# B6_32D_20230728.net
KiCad netlist of a schematic drawn in Altium Designer
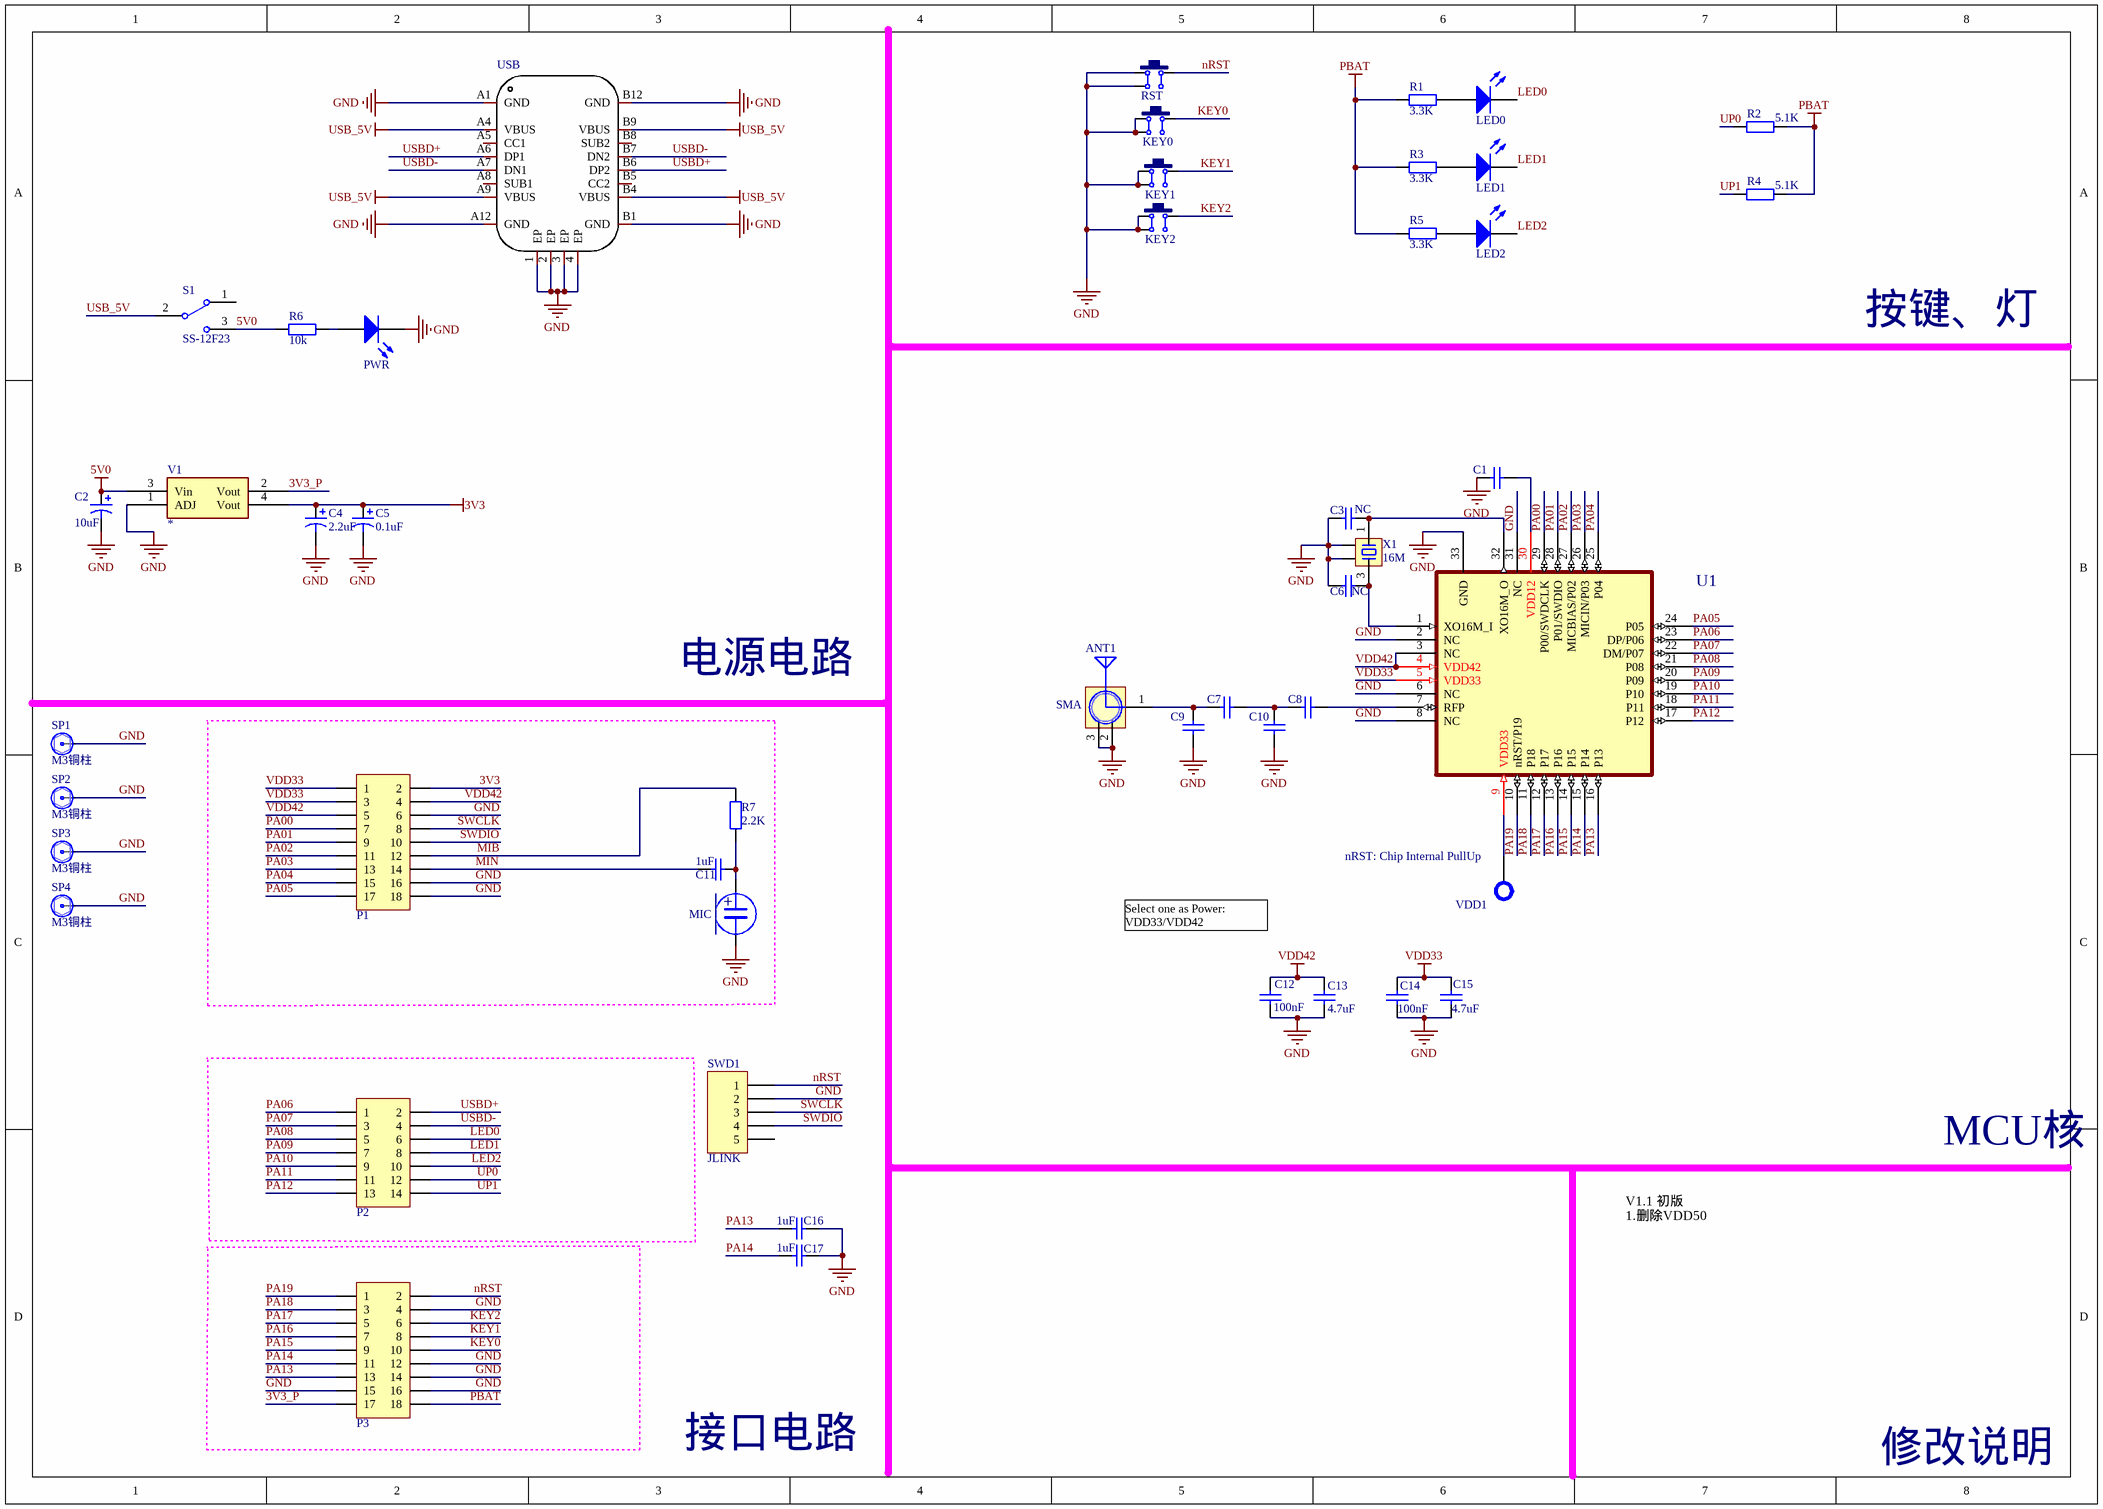
[diagram p0: B6_32D_20230728.SchDoc]

(export (version "E")
  (design (tool "Eeschema 10.0.6"))
  (components
    (comp (ref "ANT1")
      (value "SMA")
      (footprint "SMA-KE-LI")
      (description "SMA-2.4G射频天线接口")
      (libsource (lib "1.8 - WiFi天线-SMA射频座") (part "SMA"))
    )
    (comp (ref "C1")
      (value "NC")
      (footprint "C0603")
      (description "Capacitor (Semiconductor SIM Model)")
      (libsource (lib "HYBXX_Dragon") (part "Cap"))
    )
    (comp (ref "C2")
      (value "10uF")
      (footprint "HYBXX_Dragon:C0603")
      (description "Polarized Capacitor (Surface Mount)")
      (fields (field (name "PUBLISHER") "Altium Limited"))
      (libsource (lib "HYBXX_Dragon") (part "Cap Pol3"))
    )
    (comp (ref "C3")
      (value "NC")
      (footprint "C0603")
      (description "Capacitor (Semiconductor SIM Model)")
      (libsource (lib "HYBXX_Dragon") (part "Cap"))
    )
    (comp (ref "C4")
      (value "2.2uF")
      (footprint "HYBXX_Dragon:C0603")
      (description "Polarized Capacitor (Surface Mount)")
      (fields (field (name "PUBLISHER") "Altium Limited"))
      (libsource (lib "HYBXX_Dragon") (part "Cap Pol3"))
    )
    (comp (ref "C5")
      (value "0.1uF")
      (footprint "HYBXX_Dragon:C0603")
      (description "Polarized Capacitor (Surface Mount)")
      (fields (field (name "PUBLISHER") "Altium Limited"))
      (libsource (lib "HYBXX_Dragon") (part "Cap Pol3"))
    )
    (comp (ref "C6")
      (value "NC")
      (footprint "C0603")
      (description "Capacitor (Semiconductor SIM Model)")
      (libsource (lib "HYBXX_Dragon") (part "Cap"))
    )
    (comp (ref "C7")
      (value "0")
      (footprint "C0402")
      (description "Capacitor (Semiconductor SIM Model)")
      (libsource (lib "HYBXX_Dragon") (part "Cap"))
    )
    (comp (ref "C8")
      (value "0")
      (footprint "C0402")
      (description "Capacitor (Semiconductor SIM Model)")
      (libsource (lib "HYBXX_Dragon") (part "Cap"))
    )
    (comp (ref "C9")
      (value "0")
      (footprint "C0402")
      (description "Capacitor (Semiconductor SIM Model)")
      (libsource (lib "HYBXX_Dragon") (part "Cap"))
    )
    (comp (ref "C10")
      (value "0")
      (footprint "C0402")
      (description "Capacitor (Semiconductor SIM Model)")
      (libsource (lib "HYBXX_Dragon") (part "Cap"))
    )
    (comp (ref "C11")
      (value "1uF")
      (footprint "C0603")
      (description "Capacitor (Semiconductor SIM Model)")
      (libsource (lib "HYBXX_Dragon") (part "Cap"))
    )
    (comp (ref "C12")
      (value "100nF")
      (footprint "C0603")
      (description "Capacitor (Semiconductor SIM Model)")
      (libsource (lib "HYBXX_Dragon") (part "Cap"))
    )
    (comp (ref "C13")
      (value "4.7uF")
      (footprint "C0603")
      (description "Capacitor (Semiconductor SIM Model)")
      (libsource (lib "HYBXX_Dragon") (part "Cap"))
    )
    (comp (ref "C14")
      (value "100nF")
      (footprint "C0603")
      (description "Capacitor (Semiconductor SIM Model)")
      (fields (field (name "PUBLISHER") "Altium Limited"))
      (libsource (lib "Miscellaneous Devices") (part "Cap Semi"))
    )
    (comp (ref "C15")
      (value "4.7uF")
      (footprint "C0603")
      (description "Capacitor (Semiconductor SIM Model)")
      (libsource (lib "HYBXX_Dragon") (part "Cap"))
    )
    (comp (ref "C16")
      (value "1uF")
      (footprint "C0603")
      (description "Capacitor (Semiconductor SIM Model)")
      (libsource (lib "HYBXX_Dragon") (part "Cap"))
    )
    (comp (ref "C17")
      (value "1uF")
      (footprint "C0603")
      (description "Capacitor (Semiconductor SIM Model)")
      (libsource (lib "HYBXX_Dragon") (part "Cap"))
    )
    (comp (ref "KEY0")
      (value "6x6x5")
      (footprint "SW-SMD")
      (description "贴片6x6轻触开关")
      (fields (field (name "版权归属") "封装库来自淘宝 ID：黄晶宝石"))
      (libsource (lib "0.7 - 常用按键-开关") (part "TSW SMD-6x6"))
    )
    (comp (ref "KEY1")
      (value "6x6x5")
      (footprint "SW-SMD")
      (description "贴片6x6轻触开关")
      (fields (field (name "版权归属") "封装库来自淘宝 ID：黄晶宝石"))
      (libsource (lib "0.7 - 常用按键-开关") (part "TSW SMD-6x6"))
    )
    (comp (ref "KEY2")
      (value "6x6x5")
      (footprint "SW-SMD")
      (description "贴片6x6轻触开关")
      (fields (field (name "版权归属") "封装库来自淘宝 ID：黄晶宝石"))
      (libsource (lib "0.7 - 常用按键-开关") (part "TSW SMD-6x6"))
    )
    (comp (ref "LED0")
      (value "*")
      (footprint "LED_0603")
      (description "发光二极管")
      (libsource (lib "HYBXX_Dragon") (part "LED"))
    )
    (comp (ref "LED1")
      (value "*")
      (footprint "LED_0603")
      (description "发光二极管")
      (libsource (lib "HYBXX_Dragon") (part "LED"))
    )
    (comp (ref "LED2")
      (value "*")
      (footprint "LED_0603")
      (description "发光二极管")
      (libsource (lib "HYBXX_Dragon") (part "LED"))
    )
    (comp (ref "MIC")
      (value "MIC-6*5mm")
      (footprint "MIC-6*5.5mm")
      (description "电容麦克风")
      (fields (field (name "版权归属") "封装库来自淘宝 ID：黄晶宝石"))
      (libsource (lib "1.2 - 传感元件") (part "MIC1"))
    )
    (comp (ref "P1")
      (value "Header 2X11")
      (footprint "HDR2.54-LI-2x9P")
      (description "9*2P接插件")
      (fields (field (name "版权归属") "淘宝ID:黄晶宝石"))
      (libsource (lib "5.3 - 接插件-脚距2.54 (100mil) ") (part "Header 9X2"))
    )
    (comp (ref "P2")
      (value "Header 2X7")
      (footprint "HDR2.54-LI-2x7P")
      (description "7*2P接插件")
      (fields (field (name "版权归属") "封装库来自淘宝 ID：黄晶宝石"))
      (libsource (lib "5.3 - 接插件-脚距2.54 (100mil) ") (part "Header 7X2"))
    )
    (comp (ref "P3")
      (value "Header 2X11")
      (footprint "HDR2.54-LI-2x9P")
      (description "9*2P接插件")
      (fields (field (name "版权归属") "淘宝ID:黄晶宝石"))
      (libsource (lib "5.3 - 接插件-脚距2.54 (100mil) ") (part "Header 9X2"))
    )
    (comp (ref "PWR")
      (value "*")
      (footprint "LED_0603")
      (description "发光二极管")
      (libsource (lib "HYBXX_Dragon") (part "LED"))
    )
    (comp (ref "R1")
      (value "3.3K")
      (footprint "R 0603_L")
      (description "贴片电阻")
      (libsource (lib "HYBXX_Dragon") (part "Res"))
    )
    (comp (ref "R2")
      (value "5.1K")
      (footprint "R 0603_L")
      (description "贴片电阻")
      (libsource (lib "") (part "Res_1"))
    )
    (comp (ref "R3")
      (value "3.3K")
      (footprint "R 0603_L")
      (description "贴片电阻")
      (libsource (lib "HYBXX_Dragon") (part "Res"))
    )
    (comp (ref "R4")
      (value "5.1K")
      (footprint "R 0603_L")
      (description "贴片电阻")
      (libsource (lib "") (part "Res_1"))
    )
    (comp (ref "R5")
      (value "3.3K")
      (footprint "R 0603_L")
      (description "贴片电阻")
      (libsource (lib "HYBXX_Dragon") (part "Res"))
    )
    (comp (ref "R6")
      (value "10k")
      (footprint "RESC_0603")
      (description "贴片电阻")
      (libsource (lib "HYBXX_Dragon") (part "Res"))
    )
    (comp (ref "R7")
      (value "2.2K")
      (footprint "R 0603_L")
      (description "贴片电阻")
      (libsource (lib "") (part "Res_1"))
    )
    (comp (ref "RST")
      (value "6x6x5")
      (footprint "SW-SMD")
      (description "贴片6x6轻触开关")
      (fields (field (name "版权归属") "封装库来自淘宝 ID：黄晶宝石"))
      (libsource (lib "0.7 - 常用按键-开关") (part "TSW SMD-6x6"))
    )
    (comp (ref "S1")
      (value "SS-12F23")
      (footprint "SK12D07VG3")
      (description "1路波动开关")
      (fields (field (name "版权归属") "封装库来自淘宝 ID：黄晶宝石"))
      (libsource (lib "0.7 - 常用按键-开关") (part "SSW-1P"))
    )
    (comp (ref "SP1")
      (value "M3铜柱")
      (footprint "M3x21+6_L")
      (description "铜柱")
      (libsource (lib "4.1 - 未分类器件") (part "铜柱加头小焊盘"))
    )
    (comp (ref "SP2")
      (value "M3铜柱")
      (footprint "M3x21+6_L")
      (description "铜柱")
      (fields (field (name "版权归属") "封装库来自淘宝 ID：黄晶宝石"))
      (libsource (lib "4.1 - 未分类器件") (part "铜柱加头小焊盘"))
    )
    (comp (ref "SP3")
      (value "M3铜柱")
      (footprint "M3x21+6_L")
      (description "铜柱")
      (fields (field (name "版权归属") "封装库来自淘宝 ID：黄晶宝石"))
      (libsource (lib "4.1 - 未分类器件") (part "铜柱加头小焊盘"))
    )
    (comp (ref "SP4")
      (value "M3铜柱")
      (footprint "M3x21+6_L")
      (description "铜柱")
      (fields (field (name "版权归属") "封装库来自淘宝 ID：黄晶宝石"))
      (libsource (lib "4.1 - 未分类器件") (part "铜柱加头小焊盘"))
    )
    (comp (ref "SWD1")
      (value "JLINK")
      (footprint "HDR2.54-LI-5P")
      (description "Header, 5-Pin")
      (fields (field (name "PUBLISHER") "Altium Limited"))
      (libsource (lib "5.3 - 接插件-脚距2.54 (100mil) ") (part "Header 5"))
    )
    (comp (ref "U1")
      (value "C1_QFN32")
      (footprint "QFN32L_0404x0.75-0.40")
      (description "HY Dragon C 蓝牙芯片, QFN32_4x4")
      (libsource (lib "HYBXX_Dragon") (part "C1_QFN32"))
    )
    (comp (ref "USB")
      (value "KH-TYPE-C-16P")
      (footprint "USB-C-SMD_KH-TYPE-C-16P")
      (description "连接器类型:Type-C;标准:-;公母:母座;触点数量:16;端口数量:1;安装方式:卧贴;额定电流 - 电源:3A;工作温度范围:-40~+85;")
      (fields (field (name "MANUFACTURER") "kinghelm(金航标)"))
      (libsource (lib "altium-import") (part "root_0_KH-TYPE-C-16P_"))
    )
    (comp (ref "V1")
      (value "*")
      (footprint "SOT223_L")
      (description "LDO 可调节稳压芯片")
      (libsource (lib "HYBXX_Dragon") (part "AMS1117"))
    )
    (comp (ref "VDD1")
      (value "HOLE")
      (footprint "HYBXX_Dragon:TEST_PAD")
      (description "定位孔")
      (libsource (lib "HYBXX_Dragon") (part "HOLE"))
    )
    (comp (ref "X1")
      (value "16M")
      (footprint "OSC3225-mini")
      (description "4脚无源晶振")
      (fields (field (name "版权归属") "封装库来自淘宝卖家 ID：黄晶宝石"))
      (libsource (lib "2.0 - 保险丝-晶振-光耦") (part "XTAL-4P"))
    )
  )
  (nets
    (net (code "1") (name "/3V3_P") (class "Default")
      (node (ref "P3") (pin "17") (pinfunction "17_17") (pintype "passive"))
      (node (ref "V1") (pin "2") (pinfunction "Vout_2") (pintype "passive"))
    )
    (net (code "2") (name "/KEY0") (class "Default")
      (node (ref "KEY0") (pin "2") (pinfunction "2_2") (pintype "passive"))
      (node (ref "P3") (pin "10") (pinfunction "10_10") (pintype "passive"))
    )
    (net (code "3") (name "/KEY1") (class "Default")
      (node (ref "KEY1") (pin "2") (pinfunction "2_2") (pintype "passive"))
      (node (ref "P3") (pin "8") (pinfunction "8_8") (pintype "passive"))
    )
    (net (code "4") (name "/KEY2") (class "Default")
      (node (ref "KEY2") (pin "2") (pinfunction "2_2") (pintype "passive"))
      (node (ref "P3") (pin "6") (pinfunction "6_6") (pintype "passive"))
    )
    (net (code "5") (name "/LED0") (class "Default")
      (node (ref "LED0") (pin "2") (pinfunction "K_2") (pintype "passive"))
      (node (ref "P2") (pin "6") (pinfunction "6_6") (pintype "passive"))
    )
    (net (code "6") (name "/LED1") (class "Default")
      (node (ref "LED1") (pin "2") (pinfunction "K_2") (pintype "passive"))
      (node (ref "P2") (pin "8") (pinfunction "8_8") (pintype "passive"))
    )
    (net (code "7") (name "/LED2") (class "Default")
      (node (ref "LED2") (pin "2") (pinfunction "K_2") (pintype "passive"))
      (node (ref "P2") (pin "10") (pinfunction "10_10") (pintype "passive"))
    )
    (net (code "8") (name "/MIB") (class "Default")
      (node (ref "P1") (pin "12") (pinfunction "12_12") (pintype "passive"))
      (node (ref "R7") (pin "1") (pinfunction "1_1") (pintype "passive"))
    )
    (net (code "9") (name "/MIN") (class "Default")
      (node (ref "C11") (pin "2") (pinfunction "2_2") (pintype "passive"))
      (node (ref "P1") (pin "14") (pinfunction "14_14") (pintype "passive"))
    )
    (net (code "10") (name "/PA00") (class "Default")
      (node (ref "P1") (pin "7") (pinfunction "7_7") (pintype "passive"))
      (node (ref "U1") (pin "29") (pinfunction "P00/SWDCLK_29") (pintype "bidirectional"))
    )
    (net (code "11") (name "/PA01") (class "Default")
      (node (ref "P1") (pin "9") (pinfunction "9_9") (pintype "passive"))
      (node (ref "U1") (pin "28") (pinfunction "P01/SWDIO_28") (pintype "bidirectional"))
    )
    (net (code "12") (name "/PA02") (class "Default")
      (node (ref "P1") (pin "11") (pinfunction "11_11") (pintype "passive"))
      (node (ref "U1") (pin "27") (pinfunction "MICBIAS/P02_27") (pintype "bidirectional"))
    )
    (net (code "13") (name "/PA03") (class "Default")
      (node (ref "P1") (pin "13") (pinfunction "13_13") (pintype "passive"))
      (node (ref "U1") (pin "26") (pinfunction "MICIN/P03_26") (pintype "bidirectional"))
    )
    (net (code "14") (name "/PA04") (class "Default")
      (node (ref "P1") (pin "15") (pinfunction "15_15") (pintype "passive"))
      (node (ref "U1") (pin "25") (pinfunction "P04_25") (pintype "bidirectional"))
    )
    (net (code "15") (name "/PA05") (class "Default")
      (node (ref "P1") (pin "17") (pinfunction "17_17") (pintype "passive"))
      (node (ref "U1") (pin "24") (pinfunction "P05_24") (pintype "bidirectional"))
    )
    (net (code "16") (name "/PA06") (class "Default")
      (node (ref "P2") (pin "1") (pinfunction "1_1") (pintype "passive"))
      (node (ref "U1") (pin "23") (pinfunction "DP/P06_23") (pintype "bidirectional"))
    )
    (net (code "17") (name "/PA07") (class "Default")
      (node (ref "P2") (pin "3") (pinfunction "3_3") (pintype "passive"))
      (node (ref "U1") (pin "22") (pinfunction "DM/P07_22") (pintype "bidirectional"))
    )
    (net (code "18") (name "/PA08") (class "Default")
      (node (ref "P2") (pin "5") (pinfunction "5_5") (pintype "passive"))
      (node (ref "U1") (pin "21") (pinfunction "P08_21") (pintype "bidirectional"))
    )
    (net (code "19") (name "/PA09") (class "Default")
      (node (ref "P2") (pin "7") (pinfunction "7_7") (pintype "passive"))
      (node (ref "U1") (pin "20") (pinfunction "P09_20") (pintype "bidirectional"))
    )
    (net (code "20") (name "/PA10") (class "Default")
      (node (ref "P2") (pin "9") (pinfunction "9_9") (pintype "passive"))
      (node (ref "U1") (pin "19") (pinfunction "P10_19") (pintype "bidirectional"))
    )
    (net (code "21") (name "/PA11") (class "Default")
      (node (ref "P2") (pin "11") (pinfunction "11_11") (pintype "passive"))
      (node (ref "U1") (pin "18") (pinfunction "P11_18") (pintype "bidirectional"))
    )
    (net (code "22") (name "/PA12") (class "Default")
      (node (ref "P2") (pin "13") (pinfunction "13_13") (pintype "passive"))
      (node (ref "U1") (pin "17") (pinfunction "P12_17") (pintype "bidirectional"))
    )
    (net (code "23") (name "/PA13") (class "Default")
      (node (ref "C16") (pin "2") (pinfunction "2_2") (pintype "passive"))
      (node (ref "P3") (pin "13") (pinfunction "13_13") (pintype "passive"))
      (node (ref "U1") (pin "16") (pinfunction "P13_16") (pintype "bidirectional"))
    )
    (net (code "24") (name "/PA14") (class "Default")
      (node (ref "C17") (pin "2") (pinfunction "2_2") (pintype "passive"))
      (node (ref "P3") (pin "11") (pinfunction "11_11") (pintype "passive"))
      (node (ref "U1") (pin "15") (pinfunction "P14_15") (pintype "bidirectional"))
    )
    (net (code "25") (name "/PA15") (class "Default")
      (node (ref "P3") (pin "9") (pinfunction "9_9") (pintype "passive"))
      (node (ref "U1") (pin "14") (pinfunction "P15_14") (pintype "bidirectional"))
    )
    (net (code "26") (name "/PA16") (class "Default")
      (node (ref "P3") (pin "7") (pinfunction "7_7") (pintype "passive"))
      (node (ref "U1") (pin "13") (pinfunction "P16_13") (pintype "bidirectional"))
    )
    (net (code "27") (name "/PA17") (class "Default")
      (node (ref "P3") (pin "5") (pinfunction "5_5") (pintype "passive"))
      (node (ref "U1") (pin "12") (pinfunction "P17_12") (pintype "bidirectional"))
    )
    (net (code "28") (name "/PA18") (class "Default")
      (node (ref "P3") (pin "3") (pinfunction "3_3") (pintype "passive"))
      (node (ref "U1") (pin "11") (pinfunction "P18_11") (pintype "bidirectional"))
    )
    (net (code "29") (name "/PA19") (class "Default")
      (node (ref "P3") (pin "1") (pinfunction "1_1") (pintype "passive"))
      (node (ref "U1") (pin "10") (pinfunction "nRST/P19_10") (pintype "bidirectional"))
    )
    (net (code "30") (name "/SWCLK") (class "Default")
      (node (ref "P1") (pin "8") (pinfunction "8_8") (pintype "passive"))
      (node (ref "SWD1") (pin "3") (pinfunction "3_3") (pintype "passive"))
    )
    (net (code "31") (name "/SWDIO") (class "Default")
      (node (ref "P1") (pin "10") (pinfunction "10_10") (pintype "passive"))
      (node (ref "SWD1") (pin "4") (pinfunction "4_4") (pintype "passive"))
    )
    (net (code "32") (name "/UP0") (class "Default")
      (node (ref "P2") (pin "12") (pinfunction "12_12") (pintype "passive"))
      (node (ref "R2") (pin "2") (pinfunction "2_2") (pintype "passive"))
    )
    (net (code "33") (name "/UP1") (class "Default")
      (node (ref "P2") (pin "14") (pinfunction "14_14") (pintype "passive"))
      (node (ref "R4") (pin "2") (pinfunction "2_2") (pintype "passive"))
    )
    (net (code "34") (name "/USBD+") (class "Default")
      (node (ref "P2") (pin "2") (pinfunction "2_2") (pintype "passive"))
      (node (ref "USB") (pin "A6") (pinfunction "DP1_A6") (pintype "passive"))
      (node (ref "USB") (pin "B6") (pinfunction "DP2_B6") (pintype "passive"))
    )
    (net (code "35") (name "/USBD-") (class "Default")
      (node (ref "P2") (pin "4") (pinfunction "4_4") (pintype "passive"))
      (node (ref "USB") (pin "A7") (pinfunction "DN1_A7") (pintype "passive"))
      (node (ref "USB") (pin "B7") (pinfunction "DN2_B7") (pintype "passive"))
    )
    (net (code "36") (name "/nRST") (class "Default")
      (node (ref "P3") (pin "2") (pinfunction "2_2") (pintype "passive"))
      (node (ref "RST") (pin "2") (pinfunction "2_2") (pintype "passive"))
      (node (ref "SWD1") (pin "1") (pinfunction "1_1") (pintype "passive"))
    )
    (net (code "37") (name "3V3") (class "Default")
      (node (ref "C4") (pin "1") (pinfunction "1_1") (pintype "passive"))
      (node (ref "C5") (pin "1") (pinfunction "1_1") (pintype "passive"))
      (node (ref "P1") (pin "2") (pinfunction "2_2") (pintype "passive"))
      (node (ref "V1") (pin "4") (pinfunction "Vout_4") (pintype "passive"))
    )
    (net (code "38") (name "5V0") (class "Default")
      (node (ref "C2") (pin "1") (pinfunction "1_1") (pintype "passive"))
      (node (ref "R6") (pin "1") (pinfunction "1_1") (pintype "passive"))
      (node (ref "S1") (pin "3") (pinfunction "3_3") (pintype "passive"))
      (node (ref "V1") (pin "3") (pinfunction "Vin_3") (pintype "passive"))
    )
    (net (code "39") (name "GND") (class "Default")
      (node (ref "ANT1") (pin "2") (pinfunction "GND_2") (pintype "power_in"))
      (node (ref "ANT1") (pin "3") (pinfunction "GND_3") (pintype "power_in"))
      (node (ref "C1") (pin "2") (pinfunction "2_2") (pintype "passive"))
      (node (ref "C10") (pin "2") (pinfunction "2_2") (pintype "passive"))
      (node (ref "C12") (pin "1") (pinfunction "1_1") (pintype "passive"))
      (node (ref "C13") (pin "1") (pinfunction "1_1") (pintype "passive"))
      (node (ref "C14") (pin "1") (pinfunction "1_1") (pintype "passive"))
      (node (ref "C15") (pin "2") (pinfunction "2_2") (pintype "passive"))
      (node (ref "C16") (pin "1") (pinfunction "1_1") (pintype "passive"))
      (node (ref "C17") (pin "1") (pinfunction "1_1") (pintype "passive"))
      (node (ref "C2") (pin "2") (pinfunction "2_2") (pintype "passive"))
      (node (ref "C3") (pin "1") (pinfunction "1_1") (pintype "passive"))
      (node (ref "C4") (pin "2") (pinfunction "2_2") (pintype "passive"))
      (node (ref "C5") (pin "2") (pinfunction "2_2") (pintype "passive"))
      (node (ref "C6") (pin "2") (pinfunction "2_2") (pintype "passive"))
      (node (ref "C9") (pin "2") (pinfunction "2_2") (pintype "passive"))
      (node (ref "KEY0") (pin "1") (pinfunction "1_1") (pintype "passive"))
      (node (ref "KEY0") (pin "4") (pinfunction "4_4") (pintype "passive"))
      (node (ref "KEY1") (pin "1") (pinfunction "1_1") (pintype "passive"))
      (node (ref "KEY1") (pin "4") (pinfunction "4_4") (pintype "passive"))
      (node (ref "KEY2") (pin "1") (pinfunction "1_1") (pintype "passive"))
      (node (ref "KEY2") (pin "4") (pinfunction "4_4") (pintype "passive"))
      (node (ref "MIC") (pin "2") (pinfunction "2_2") (pintype "passive"))
      (node (ref "P1") (pin "16") (pinfunction "16_16") (pintype "passive"))
      (node (ref "P1") (pin "18") (pinfunction "18_18") (pintype "passive"))
      (node (ref "P1") (pin "6") (pinfunction "6_6") (pintype "passive"))
      (node (ref "P3") (pin "12") (pinfunction "12_12") (pintype "passive"))
      (node (ref "P3") (pin "14") (pinfunction "14_14") (pintype "passive"))
      (node (ref "P3") (pin "15") (pinfunction "15_15") (pintype "passive"))
      (node (ref "P3") (pin "16") (pinfunction "16_16") (pintype "passive"))
      (node (ref "P3") (pin "4") (pinfunction "4_4") (pintype "passive"))
      (node (ref "PWR") (pin "2") (pinfunction "K_2") (pintype "passive"))
      (node (ref "RST") (pin "1") (pinfunction "1_1") (pintype "passive"))
      (node (ref "RST") (pin "4") (pinfunction "4_4") (pintype "passive"))
      (node (ref "SP1") (pin "1") (pinfunction "1_1") (pintype "passive"))
      (node (ref "SP2") (pin "1") (pinfunction "1_1") (pintype "passive"))
      (node (ref "SP3") (pin "1") (pinfunction "1_1") (pintype "passive"))
      (node (ref "SP4") (pin "1") (pinfunction "1_1") (pintype "passive"))
      (node (ref "SWD1") (pin "2") (pinfunction "2_2") (pintype "passive"))
      (node (ref "U1") (pin "2") (pinfunction "NC_2") (pintype "passive"))
      (node (ref "U1") (pin "31") (pinfunction "NC_31") (pintype "passive"))
      (node (ref "U1") (pin "33") (pinfunction "GND_33") (pintype "passive"))
      (node (ref "U1") (pin "6") (pinfunction "NC_6") (pintype "passive"))
      (node (ref "U1") (pin "8") (pinfunction "NC_8") (pintype "passive"))
      (node (ref "USB") (pin "1") (pinfunction "EP_1") (pintype "passive"))
      (node (ref "USB") (pin "2") (pinfunction "EP_2") (pintype "passive"))
      (node (ref "USB") (pin "3") (pinfunction "EP_3") (pintype "passive"))
      (node (ref "USB") (pin "4") (pinfunction "EP_4") (pintype "passive"))
      (node (ref "USB") (pin "A1") (pinfunction "GND_A1") (pintype "passive"))
      (node (ref "USB") (pin "A12") (pinfunction "GND_A12") (pintype "passive"))
      (node (ref "USB") (pin "B1") (pinfunction "GND_B1") (pintype "passive"))
      (node (ref "USB") (pin "B12") (pinfunction "GND_B12") (pintype "passive"))
      (node (ref "V1") (pin "1") (pinfunction "ADJ_1") (pintype "passive"))
      (node (ref "X1") (pin "2") (pinfunction "2_2") (pintype "passive"))
      (node (ref "X1") (pin "4") (pinfunction "4_4") (pintype "passive"))
    )
    (net (code "40") (name "Net-(ANT1-ANT)") (class "Default")
      (node (ref "ANT1") (pin "1") (pinfunction "ANT_1") (pintype "passive"))
      (node (ref "C7") (pin "2") (pinfunction "2_2") (pintype "passive"))
      (node (ref "C9") (pin "1") (pinfunction "1_1") (pintype "passive"))
    )
    (net (code "41") (name "Net-(C10-Pad1)") (class "Default")
      (node (ref "C10") (pin "1") (pinfunction "1_1") (pintype "passive"))
      (node (ref "C7") (pin "1") (pinfunction "1_1") (pintype "passive"))
      (node (ref "C8") (pin "2") (pinfunction "2_2") (pintype "passive"))
    )
    (net (code "42") (name "Net-(C11-Pad1)") (class "Default")
      (node (ref "C11") (pin "1") (pinfunction "1_1") (pintype "passive"))
      (node (ref "MIC") (pin "1") (pinfunction "1_1") (pintype "passive"))
      (node (ref "R7") (pin "2") (pinfunction "2_2") (pintype "passive"))
    )
    (net (code "43") (name "Net-(LED0-A)") (class "Default")
      (node (ref "LED0") (pin "1") (pinfunction "A_1") (pintype "passive"))
      (node (ref "R1") (pin "2") (pinfunction "2_2") (pintype "passive"))
    )
    (net (code "44") (name "Net-(LED1-A)") (class "Default")
      (node (ref "LED1") (pin "1") (pinfunction "A_1") (pintype "passive"))
      (node (ref "R3") (pin "2") (pinfunction "2_2") (pintype "passive"))
    )
    (net (code "45") (name "Net-(LED2-A)") (class "Default")
      (node (ref "LED2") (pin "1") (pinfunction "A_1") (pintype "passive"))
      (node (ref "R5") (pin "2") (pinfunction "2_2") (pintype "passive"))
    )
    (net (code "46") (name "Net-(PWR-A)") (class "Default")
      (node (ref "PWR") (pin "1") (pinfunction "A_1") (pintype "passive"))
      (node (ref "R6") (pin "2") (pinfunction "2_2") (pintype "passive"))
    )
    (net (code "47") (name "Net-(U1-RFP)") (class "Default")
      (node (ref "C8") (pin "1") (pinfunction "1_1") (pintype "passive"))
      (node (ref "U1") (pin "7") (pinfunction "RFP_7") (pintype "bidirectional"))
    )
    (net (code "48") (name "Net-(U1-VDD12)") (class "Default")
      (node (ref "C1") (pin "1") (pinfunction "1_1") (pintype "passive"))
      (node (ref "U1") (pin "30") (pinfunction "VDD12_30") (pintype "passive"))
    )
    (net (code "49") (name "Net-(U1-XO16M_I)") (class "Default")
      (node (ref "C6") (pin "1") (pinfunction "1_1") (pintype "passive"))
      (node (ref "U1") (pin "1") (pinfunction "XO16M_I_1") (pintype "input"))
      (node (ref "X1") (pin "3") (pinfunction "3_3") (pintype "passive"))
    )
    (net (code "50") (name "Net-(U1-XO16M_O)") (class "Default")
      (node (ref "C3") (pin "2") (pinfunction "2_2") (pintype "passive"))
      (node (ref "U1") (pin "32") (pinfunction "XO16M_O_32") (pintype "output"))
      (node (ref "X1") (pin "1") (pinfunction "1_1") (pintype "passive"))
    )
    (net (code "51") (name "Net-(VDD1-HOLE)") (class "Default")
      (node (ref "U1") (pin "9") (pinfunction "VDD33_9") (pintype "input"))
      (node (ref "VDD1") (pin "1") (pinfunction "HOLE_1") (pintype "passive"))
    )
    (net (code "52") (name "PBAT") (class "Default")
      (node (ref "P3") (pin "18") (pinfunction "18_18") (pintype "passive"))
      (node (ref "R1") (pin "1") (pinfunction "1_1") (pintype "passive"))
      (node (ref "R2") (pin "1") (pinfunction "1_1") (pintype "passive"))
      (node (ref "R3") (pin "1") (pinfunction "1_1") (pintype "passive"))
      (node (ref "R4") (pin "1") (pinfunction "1_1") (pintype "passive"))
      (node (ref "R5") (pin "1") (pinfunction "1_1") (pintype "passive"))
    )
    (net (code "53") (name "USB_5V") (class "Default")
      (node (ref "S1") (pin "2") (pinfunction "2_2") (pintype "passive"))
      (node (ref "USB") (pin "A4") (pinfunction "VBUS_A4") (pintype "passive"))
      (node (ref "USB") (pin "A9") (pinfunction "VBUS_A9") (pintype "passive"))
      (node (ref "USB") (pin "B4") (pinfunction "VBUS_B4") (pintype "passive"))
      (node (ref "USB") (pin "B9") (pinfunction "VBUS_B9") (pintype "passive"))
    )
    (net (code "54") (name "VDD33") (class "Default")
      (node (ref "C14") (pin "2") (pinfunction "2_2") (pintype "passive"))
      (node (ref "C15") (pin "1") (pinfunction "1_1") (pintype "passive"))
      (node (ref "P1") (pin "1") (pinfunction "1_1") (pintype "passive"))
      (node (ref "P1") (pin "3") (pinfunction "3_3") (pintype "passive"))
      (node (ref "U1") (pin "5") (pinfunction "VDD33_5") (pintype "input"))
    )
    (net (code "55") (name "VDD42") (class "Default")
      (node (ref "C12") (pin "2") (pinfunction "2_2") (pintype "passive"))
      (node (ref "C13") (pin "2") (pinfunction "2_2") (pintype "passive"))
      (node (ref "P1") (pin "4") (pinfunction "4_4") (pintype "passive"))
      (node (ref "P1") (pin "5") (pinfunction "5_5") (pintype "passive"))
      (node (ref "U1") (pin "3") (pinfunction "NC_3") (pintype "passive"))
      (node (ref "U1") (pin "4") (pinfunction "VDD42_4") (pintype "input"))
    )
    (net (code "56") (name "unconnected-(KEY0-Pad3)") (class "Default")
      (node (ref "KEY0") (pin "3") (pinfunction "3_3") (pintype "passive"))
    )
    (net (code "57") (name "unconnected-(KEY1-Pad3)") (class "Default")
      (node (ref "KEY1") (pin "3") (pinfunction "3_3") (pintype "passive"))
    )
    (net (code "58") (name "unconnected-(KEY2-Pad3)") (class "Default")
      (node (ref "KEY2") (pin "3") (pinfunction "3_3") (pintype "passive"))
    )
    (net (code "59") (name "unconnected-(RST-Pad3)") (class "Default")
      (node (ref "RST") (pin "3") (pinfunction "3_3") (pintype "passive"))
    )
    (net (code "60") (name "unconnected-(S1-Pad1)") (class "Default")
      (node (ref "S1") (pin "1") (pinfunction "1_1") (pintype "passive"))
    )
    (net (code "61") (name "unconnected-(SWD1-Pad5)") (class "Default")
      (node (ref "SWD1") (pin "5") (pinfunction "5_5") (pintype "passive"))
    )
    (net (code "62") (name "unconnected-(USB-CC1-PadA5)") (class "Default")
      (node (ref "USB") (pin "A5") (pinfunction "CC1_A5") (pintype "passive"))
    )
    (net (code "63") (name "unconnected-(USB-CC2-PadB5)") (class "Default")
      (node (ref "USB") (pin "B5") (pinfunction "CC2_B5") (pintype "passive"))
    )
    (net (code "64") (name "unconnected-(USB-SUB1-PadA8)") (class "Default")
      (node (ref "USB") (pin "A8") (pinfunction "SUB1_A8") (pintype "passive"))
    )
    (net (code "65") (name "unconnected-(USB-SUB2-PadB8)") (class "Default")
      (node (ref "USB") (pin "B8") (pinfunction "SUB2_B8") (pintype "passive"))
    )
  )
)
